# Sheet_ESP8266_SIM800C.net
KiCad netlist of a schematic drawn in Altium Designer
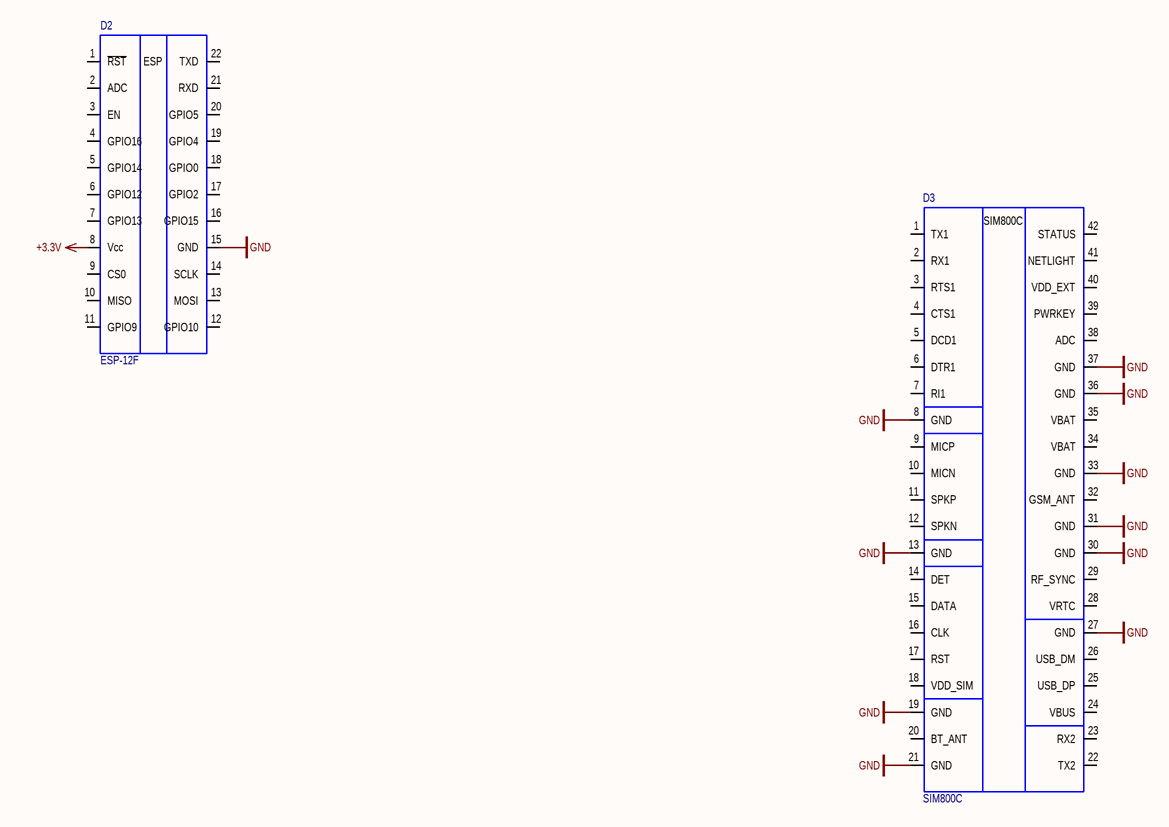
[diagram p0: Sheet_ESP8266_SIM800C.SchDoc]

(export (version "E")
  (design (tool "Eeschema 10.0.6"))
  (components
    (comp (ref "D2")
      (value "ESP-12F")
      (footprint "ESP8266 ESP-12-E")
      (libsource (lib "Integrated_Library_Smart_Switchboard") (part "ESP-12F"))
    )
    (comp (ref "D3")
      (value "SIM800C")
      (footprint "SIM800C")
      (libsource (lib "Integrated_Library_Smart_Switchboard") (part "SIM800C"))
    )
  )
  (nets
    (net (code "1") (name "+3.3V") (class "Default")
      (node (ref "D2") (pin "8") (pinfunction "Vcc_8") (pintype "passive"))
    )
    (net (code "2") (name "GND") (class "Default")
      (node (ref "D2") (pin "15") (pinfunction "GND_15") (pintype "passive"))
      (node (ref "D3") (pin "13") (pinfunction "GND_13") (pintype "passive"))
      (node (ref "D3") (pin "19") (pinfunction "GND_19") (pintype "passive"))
      (node (ref "D3") (pin "21") (pinfunction "GND_21") (pintype "passive"))
      (node (ref "D3") (pin "27") (pinfunction "GND_27") (pintype "passive"))
      (node (ref "D3") (pin "30") (pinfunction "GND_30") (pintype "passive"))
      (node (ref "D3") (pin "31") (pinfunction "GND_31") (pintype "passive"))
      (node (ref "D3") (pin "33") (pinfunction "GND_33") (pintype "passive"))
      (node (ref "D3") (pin "36") (pinfunction "GND_36") (pintype "passive"))
      (node (ref "D3") (pin "37") (pinfunction "GND_37") (pintype "passive"))
      (node (ref "D3") (pin "8") (pinfunction "GND_8") (pintype "passive"))
    )
    (net (code "3") (name "unconnected-(D2-ADC-Pad2)") (class "Default")
      (node (ref "D2") (pin "2") (pinfunction "ADC_2") (pintype "passive"))
    )
    (net (code "4") (name "unconnected-(D2-CS0-Pad9)") (class "Default")
      (node (ref "D2") (pin "9") (pinfunction "CS0_9") (pintype "passive"))
    )
    (net (code "5") (name "unconnected-(D2-EN-Pad3)") (class "Default")
      (node (ref "D2") (pin "3") (pinfunction "EN_3") (pintype "passive"))
    )
    (net (code "6") (name "unconnected-(D2-GPIO0-Pad18)") (class "Default")
      (node (ref "D2") (pin "18") (pinfunction "GPIO0_18") (pintype "passive"))
    )
    (net (code "7") (name "unconnected-(D2-GPIO2-Pad17)") (class "Default")
      (node (ref "D2") (pin "17") (pinfunction "GPIO2_17") (pintype "passive"))
    )
    (net (code "8") (name "unconnected-(D2-GPIO4-Pad19)") (class "Default")
      (node (ref "D2") (pin "19") (pinfunction "GPIO4_19") (pintype "passive"))
    )
    (net (code "9") (name "unconnected-(D2-GPIO5-Pad20)") (class "Default")
      (node (ref "D2") (pin "20") (pinfunction "GPIO5_20") (pintype "passive"))
    )
    (net (code "10") (name "unconnected-(D2-GPIO9-Pad11)") (class "Default")
      (node (ref "D2") (pin "11") (pinfunction "GPIO9_11") (pintype "passive"))
    )
    (net (code "11") (name "unconnected-(D2-GPIO10-Pad12)") (class "Default")
      (node (ref "D2") (pin "12") (pinfunction "GPIO10_12") (pintype "passive"))
    )
    (net (code "12") (name "unconnected-(D2-GPIO12-Pad6)") (class "Default")
      (node (ref "D2") (pin "6") (pinfunction "GPIO12_6") (pintype "passive"))
    )
    (net (code "13") (name "unconnected-(D2-GPIO13-Pad7)") (class "Default")
      (node (ref "D2") (pin "7") (pinfunction "GPIO13_7") (pintype "passive"))
    )
    (net (code "14") (name "unconnected-(D2-GPIO14-Pad5)") (class "Default")
      (node (ref "D2") (pin "5") (pinfunction "GPIO14_5") (pintype "passive"))
    )
    (net (code "15") (name "unconnected-(D2-GPIO15-Pad16)") (class "Default")
      (node (ref "D2") (pin "16") (pinfunction "GPIO15_16") (pintype "passive"))
    )
    (net (code "16") (name "unconnected-(D2-GPIO16-Pad4)") (class "Default")
      (node (ref "D2") (pin "4") (pinfunction "GPIO16_4") (pintype "passive"))
    )
    (net (code "17") (name "unconnected-(D2-MISO-Pad10)") (class "Default")
      (node (ref "D2") (pin "10") (pinfunction "MISO_10") (pintype "passive"))
    )
    (net (code "18") (name "unconnected-(D2-MOSI-Pad13)") (class "Default")
      (node (ref "D2") (pin "13") (pinfunction "MOSI_13") (pintype "passive"))
    )
    (net (code "19") (name "unconnected-(D2-RXD-Pad21)") (class "Default")
      (node (ref "D2") (pin "21") (pinfunction "RXD_21") (pintype "passive"))
    )
    (net (code "20") (name "unconnected-(D2-SCLK-Pad14)") (class "Default")
      (node (ref "D2") (pin "14") (pinfunction "SCLK_14") (pintype "passive"))
    )
    (net (code "21") (name "unconnected-(D2-TXD-Pad22)") (class "Default")
      (node (ref "D2") (pin "22") (pinfunction "TXD_22") (pintype "passive"))
    )
    (net (code "22") (name "unconnected-(D2-~{RST}-Pad1)") (class "Default")
      (node (ref "D2") (pin "1") (pinfunction "~{RST}_1") (pintype "passive"))
    )
    (net (code "23") (name "unconnected-(D3-ADC-Pad38)") (class "Default")
      (node (ref "D3") (pin "38") (pinfunction "ADC_38") (pintype "passive"))
    )
    (net (code "24") (name "unconnected-(D3-BT_ANT-Pad20)") (class "Default")
      (node (ref "D3") (pin "20") (pinfunction "BT_ANT_20") (pintype "passive"))
    )
    (net (code "25") (name "unconnected-(D3-CLK-Pad16)") (class "Default")
      (node (ref "D3") (pin "16") (pinfunction "CLK_16") (pintype "passive"))
    )
    (net (code "26") (name "unconnected-(D3-CTS1-Pad4)") (class "Default")
      (node (ref "D3") (pin "4") (pinfunction "CTS1_4") (pintype "passive"))
    )
    (net (code "27") (name "unconnected-(D3-DATA-Pad15)") (class "Default")
      (node (ref "D3") (pin "15") (pinfunction "DATA_15") (pintype "passive"))
    )
    (net (code "28") (name "unconnected-(D3-DCD1-Pad5)") (class "Default")
      (node (ref "D3") (pin "5") (pinfunction "DCD1_5") (pintype "passive"))
    )
    (net (code "29") (name "unconnected-(D3-DET-Pad14)") (class "Default")
      (node (ref "D3") (pin "14") (pinfunction "DET_14") (pintype "passive"))
    )
    (net (code "30") (name "unconnected-(D3-DTR1-Pad6)") (class "Default")
      (node (ref "D3") (pin "6") (pinfunction "DTR1_6") (pintype "passive"))
    )
    (net (code "31") (name "unconnected-(D3-GSM_ANT-Pad32)") (class "Default")
      (node (ref "D3") (pin "32") (pinfunction "GSM_ANT_32") (pintype "passive"))
    )
    (net (code "32") (name "unconnected-(D3-MICN-Pad10)") (class "Default")
      (node (ref "D3") (pin "10") (pinfunction "MICN_10") (pintype "passive"))
    )
    (net (code "33") (name "unconnected-(D3-MICP-Pad9)") (class "Default")
      (node (ref "D3") (pin "9") (pinfunction "MICP_9") (pintype "passive"))
    )
    (net (code "34") (name "unconnected-(D3-NETLIGHT-Pad41)") (class "Default")
      (node (ref "D3") (pin "41") (pinfunction "NETLIGHT_41") (pintype "passive"))
    )
    (net (code "35") (name "unconnected-(D3-PWRKEY-Pad39)") (class "Default")
      (node (ref "D3") (pin "39") (pinfunction "PWRKEY_39") (pintype "passive"))
    )
    (net (code "36") (name "unconnected-(D3-RF_SYNC-Pad29)") (class "Default")
      (node (ref "D3") (pin "29") (pinfunction "RF_SYNC_29") (pintype "passive"))
    )
    (net (code "37") (name "unconnected-(D3-RI1-Pad7)") (class "Default")
      (node (ref "D3") (pin "7") (pinfunction "RI1_7") (pintype "passive"))
    )
    (net (code "38") (name "unconnected-(D3-RST-Pad17)") (class "Default")
      (node (ref "D3") (pin "17") (pinfunction "RST_17") (pintype "passive"))
    )
    (net (code "39") (name "unconnected-(D3-RTS1-Pad3)") (class "Default")
      (node (ref "D3") (pin "3") (pinfunction "RTS1_3") (pintype "passive"))
    )
    (net (code "40") (name "unconnected-(D3-RX1-Pad2)") (class "Default")
      (node (ref "D3") (pin "2") (pinfunction "RX1_2") (pintype "passive"))
    )
    (net (code "41") (name "unconnected-(D3-RX2-Pad23)") (class "Default")
      (node (ref "D3") (pin "23") (pinfunction "RX2_23") (pintype "passive"))
    )
    (net (code "42") (name "unconnected-(D3-SPKN-Pad12)") (class "Default")
      (node (ref "D3") (pin "12") (pinfunction "SPKN_12") (pintype "passive"))
    )
    (net (code "43") (name "unconnected-(D3-SPKP-Pad11)") (class "Default")
      (node (ref "D3") (pin "11") (pinfunction "SPKP_11") (pintype "passive"))
    )
    (net (code "44") (name "unconnected-(D3-STATUS-Pad42)") (class "Default")
      (node (ref "D3") (pin "42") (pinfunction "STATUS_42") (pintype "passive"))
    )
    (net (code "45") (name "unconnected-(D3-TX1-Pad1)") (class "Default")
      (node (ref "D3") (pin "1") (pinfunction "TX1_1") (pintype "passive"))
    )
    (net (code "46") (name "unconnected-(D3-TX2-Pad22)") (class "Default")
      (node (ref "D3") (pin "22") (pinfunction "TX2_22") (pintype "passive"))
    )
    (net (code "47") (name "unconnected-(D3-USB_DM-Pad26)") (class "Default")
      (node (ref "D3") (pin "26") (pinfunction "USB_DM_26") (pintype "passive"))
    )
    (net (code "48") (name "unconnected-(D3-USB_DP-Pad25)") (class "Default")
      (node (ref "D3") (pin "25") (pinfunction "USB_DP_25") (pintype "passive"))
    )
    (net (code "49") (name "unconnected-(D3-VBAT-Pad34)") (class "Default")
      (node (ref "D3") (pin "34") (pinfunction "VBAT_34") (pintype "passive"))
    )
    (net (code "50") (name "unconnected-(D3-VBAT-Pad35)") (class "Default")
      (node (ref "D3") (pin "35") (pinfunction "VBAT_35") (pintype "passive"))
    )
    (net (code "51") (name "unconnected-(D3-VBUS-Pad24)") (class "Default")
      (node (ref "D3") (pin "24") (pinfunction "VBUS_24") (pintype "passive"))
    )
    (net (code "52") (name "unconnected-(D3-VDD_EXT-Pad40)") (class "Default")
      (node (ref "D3") (pin "40") (pinfunction "VDD_EXT_40") (pintype "passive"))
    )
    (net (code "53") (name "unconnected-(D3-VDD_SIM-Pad18)") (class "Default")
      (node (ref "D3") (pin "18") (pinfunction "VDD_SIM_18") (pintype "passive"))
    )
    (net (code "54") (name "unconnected-(D3-VRTC-Pad28)") (class "Default")
      (node (ref "D3") (pin "28") (pinfunction "VRTC_28") (pintype "passive"))
    )
  )
)
